# Power_Supply.net
KiCad netlist of a schematic drawn in Altium Designer
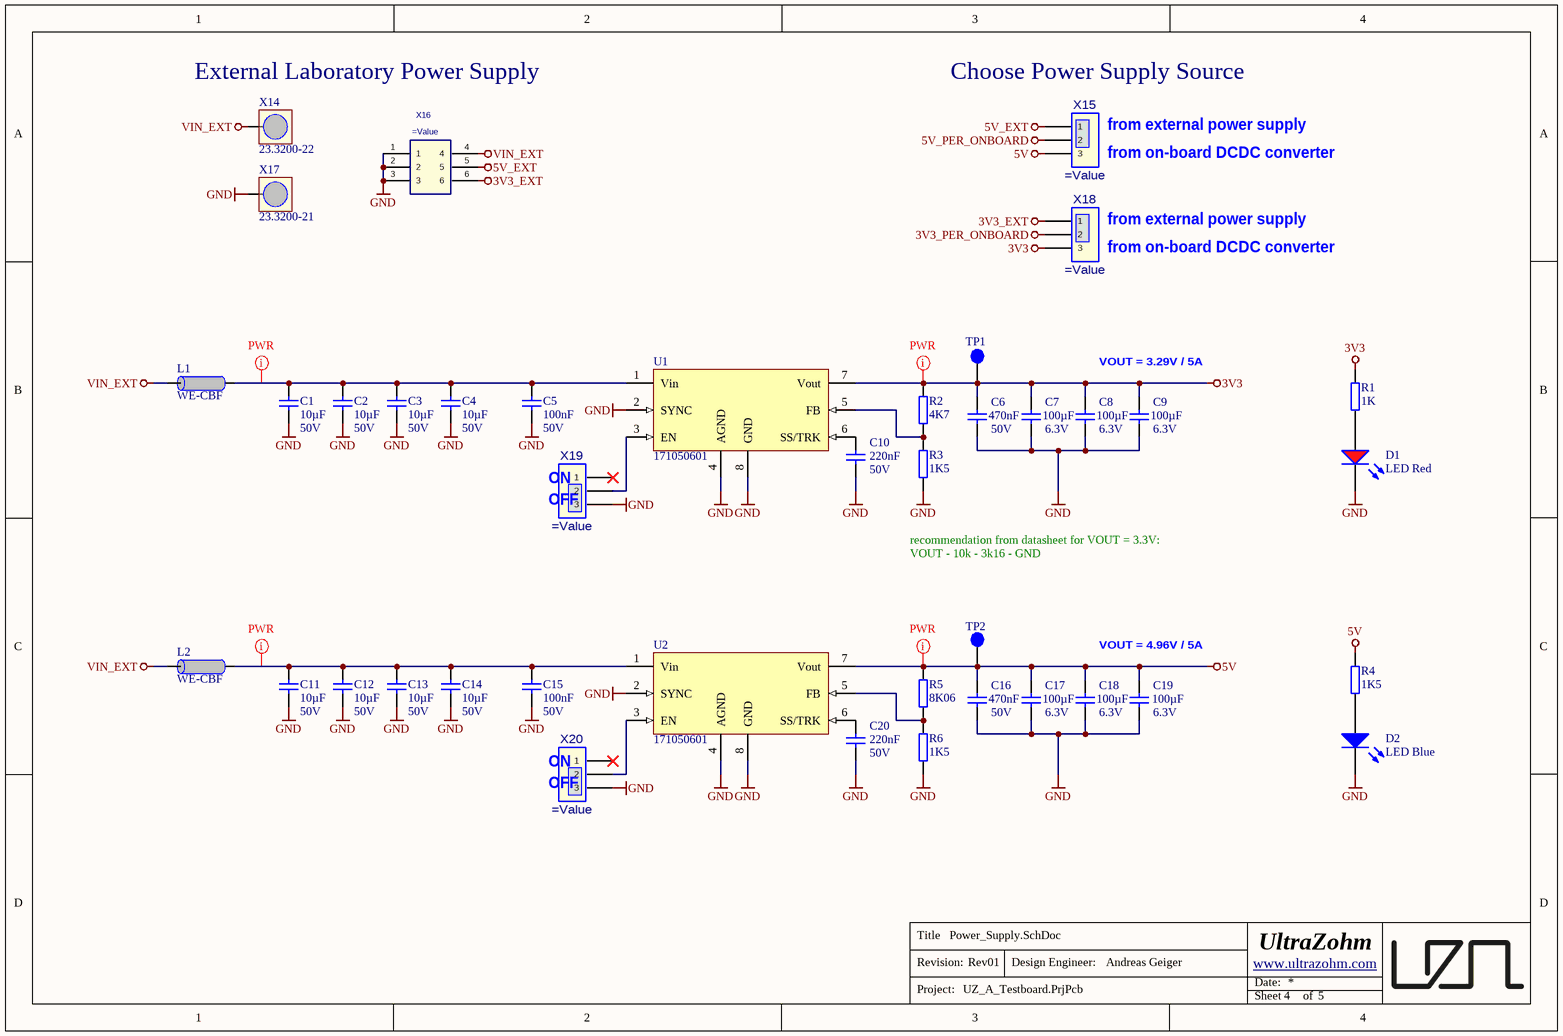
[diagram p0: Power_Supply.SchDoc]

(export (version "E")
  (design (tool "Eeschema 10.0.6"))
  (components
    (comp (ref "C1")
      (value "10µF")
      (footprint "CAPC3216X180N_V")
      (description "KON 10µF 50V X5R 10%  SMD BF 3216 (1206)")
      (fields (field (name "VOLTAGE") "50V") (field (name "TOLERANCE") "10%"))
      (libsource (lib "TE") (part "CAP-NP"))
    )
    (comp (ref "C2")
      (value "10µF")
      (footprint "CAPC3216X180N_V")
      (description "KON 10µF 50V X5R 10%  SMD BF 3216 (1206)")
      (fields (field (name "VOLTAGE") "50V") (field (name "TOLERANCE") "10%"))
      (libsource (lib "TE") (part "CAP-NP"))
    )
    (comp (ref "C3")
      (value "10µF")
      (footprint "CAPC3216X180N_V")
      (description "KON 10µF 50V X5R 10%  SMD BF 3216 (1206)")
      (fields (field (name "VOLTAGE") "50V") (field (name "TOLERANCE") "10%"))
      (libsource (lib "TE") (part "CAP-NP"))
    )
    (comp (ref "C4")
      (value "10µF")
      (footprint "CAPC3216X180N_V")
      (description "KON 10µF 50V X5R 10%  SMD BF 3216 (1206)")
      (fields (field (name "VOLTAGE") "50V") (field (name "TOLERANCE") "10%"))
      (libsource (lib "TE") (part "CAP-NP"))
    )
    (comp (ref "C5")
      (value "100nF")
      (footprint "CAPC1608X90N_V")
      (description "KON 100nF 50V X7R ±10% SMD BF 1608 (0603)")
      (fields (field (name "TOLERANCE") "±10%") (field (name "VOLTAGE") "50V"))
      (libsource (lib "TE") (part "CAP-NP"))
    )
    (comp (ref "C6")
      (value "470nF")
      (footprint "CAPC1608X90N_V")
      (description "KON 470nF 50V X7R SMD  BF 1608 (0603)")
      (fields (field (name "VOLTAGE") "50V"))
      (libsource (lib "TE") (part "CAP-NP"))
    )
    (comp (ref "C7")
      (value "100µF")
      (footprint "CAPC3216X180N_V")
      (description "KON 100µF 6,3V X5R 20% SMD BF 3216 (1206)")
      (fields (field (name "VOLTAGE") "6.3V") (field (name "TOLERANCE") "20%"))
      (libsource (lib "TE") (part "CAP-NP"))
    )
    (comp (ref "C8")
      (value "100µF")
      (footprint "CAPC3216X180N_V")
      (description "KON 100µF 6,3V X5R 20% SMD BF 3216 (1206)")
      (fields (field (name "VOLTAGE") "6.3V") (field (name "TOLERANCE") "20%"))
      (libsource (lib "TE") (part "CAP-NP"))
    )
    (comp (ref "C9")
      (value "100µF")
      (footprint "CAPC3216X180N_V")
      (description "KON 100µF 6,3V X5R 20% SMD BF 3216 (1206)")
      (fields (field (name "VOLTAGE") "6.3V") (field (name "TOLERANCE") "20%"))
      (libsource (lib "TE") (part "CAP-NP"))
    )
    (comp (ref "C10")
      (value "220nF")
      (footprint "CAPC1608X90N_V")
      (description "KON 220nF 50V X7R ±10% SMD BF 1608 (0603)")
      (fields (field (name "TOLERANCE") "±10%") (field (name "VOLTAGE") "50V"))
      (libsource (lib "TE") (part "CAP-NP"))
    )
    (comp (ref "C11")
      (value "10µF")
      (footprint "CAPC3216X180N_V")
      (description "KON 10µF 50V X5R 10%  SMD BF 3216 (1206)")
      (fields (field (name "VOLTAGE") "50V") (field (name "TOLERANCE") "10%"))
      (libsource (lib "TE") (part "CAP-NP"))
    )
    (comp (ref "C12")
      (value "10µF")
      (footprint "CAPC3216X180N_V")
      (description "KON 10µF 50V X5R 10%  SMD BF 3216 (1206)")
      (fields (field (name "VOLTAGE") "50V") (field (name "TOLERANCE") "10%"))
      (libsource (lib "TE") (part "CAP-NP"))
    )
    (comp (ref "C13")
      (value "10µF")
      (footprint "CAPC3216X180N_V")
      (description "KON 10µF 50V X5R 10%  SMD BF 3216 (1206)")
      (fields (field (name "VOLTAGE") "50V") (field (name "TOLERANCE") "10%"))
      (libsource (lib "TE") (part "CAP-NP"))
    )
    (comp (ref "C14")
      (value "10µF")
      (footprint "CAPC3216X180N_V")
      (description "KON 10µF 50V X5R 10%  SMD BF 3216 (1206)")
      (fields (field (name "VOLTAGE") "50V") (field (name "TOLERANCE") "10%"))
      (libsource (lib "TE") (part "CAP-NP"))
    )
    (comp (ref "C15")
      (value "100nF")
      (footprint "CAPC1608X90N_V")
      (description "KON 100nF 50V X7R ±10% SMD BF 1608 (0603)")
      (fields (field (name "TOLERANCE") "±10%") (field (name "VOLTAGE") "50V"))
      (libsource (lib "TE") (part "CAP-NP"))
    )
    (comp (ref "C16")
      (value "470nF")
      (footprint "CAPC1608X90N_V")
      (description "KON 470nF 50V X7R SMD  BF 1608 (0603)")
      (fields (field (name "VOLTAGE") "50V"))
      (libsource (lib "TE") (part "CAP-NP"))
    )
    (comp (ref "C17")
      (value "100µF")
      (footprint "CAPC3216X180N_V")
      (description "KON 100µF 6,3V X5R 20% SMD BF 3216 (1206)")
      (fields (field (name "VOLTAGE") "6.3V") (field (name "TOLERANCE") "20%"))
      (libsource (lib "TE") (part "CAP-NP"))
    )
    (comp (ref "C18")
      (value "100µF")
      (footprint "CAPC3216X180N_V")
      (description "KON 100µF 6,3V X5R 20% SMD BF 3216 (1206)")
      (fields (field (name "VOLTAGE") "6.3V") (field (name "TOLERANCE") "20%"))
      (libsource (lib "TE") (part "CAP-NP"))
    )
    (comp (ref "C19")
      (value "100µF")
      (footprint "CAPC3216X180N_V")
      (description "KON 100µF 6,3V X5R 20% SMD BF 3216 (1206)")
      (fields (field (name "VOLTAGE") "6.3V") (field (name "TOLERANCE") "20%"))
      (libsource (lib "TE") (part "CAP-NP"))
    )
    (comp (ref "C20")
      (value "220nF")
      (footprint "CAPC1608X90N_V")
      (description "KON 220nF 50V X7R ±10% SMD BF 1608 (0603)")
      (fields (field (name "TOLERANCE") "±10%") (field (name "VOLTAGE") "50V"))
      (libsource (lib "TE") (part "CAP-NP"))
    )
    (comp (ref "D1")
      (value "LED Red")
      (footprint "WL-SMCW_0603")
      (description "LED RED 520~625NM 90~100MCD@20MA TOP VIEW 0603 ROHS")
      (fields
        (field (name "MANUFACTURER PART NUMBER") "KT-0603R")
        (field (name "MANUFACTURER") "Hubei KENTO Elec")
        (field (name "CREATED FROM") "T. Wendt")
      )
      (libsource (lib "user") (part "LED_Red"))
    )
    (comp (ref "D2")
      (value "LED Blue")
      (footprint "WL-SMCW_0603")
      (description "LED BLUE 465~475NM 11.5~28.5MCD@5MA TOP VIEW 0603 ROHS")
      (fields
        (field (name "MANUFACTURER PART NUMBER") "19-217/BHC-ZL1M2RY/3T")
        (field (name "MANUFACTURER") "Everlight Elec")
        (field (name "CREATED FROM") "T. Wendt")
      )
      (libsource (lib "user") (part "LED_Blue"))
    )
    (comp (ref "L1")
      (value "WE-CBF")
      (footprint "INDC2012X92N_V")
      (description "Ferritdurchführung SMD 0805")
      (fields (field (name "VOLTAGE") "2000mA"))
      (libsource (lib "TE") (part "Ferritperle"))
    )
    (comp (ref "L2")
      (value "WE-CBF")
      (footprint "INDC2012X92N_V")
      (description "Ferritdurchführung SMD 0805")
      (fields (field (name "VOLTAGE") "2000mA"))
      (libsource (lib "TE") (part "Ferritperle"))
    )
    (comp (ref "R1")
      (value "1K")
      (footprint "RESC1608X55N_V")
      (description "WID SMD 1K 1% 0,1W")
      (fields (field (name "TOLERANCE") "1%"))
      (libsource (lib "TE") (part "RES"))
    )
    (comp (ref "R2")
      (value "4K7")
      (footprint "RESC1608X55N_V")
      (description "WID SMD 4K7 1% 0,1W BF 1608 (0603)")
      (fields (field (name "TOLERANCE") "1%"))
      (libsource (lib "TE") (part "RES"))
    )
    (comp (ref "R3")
      (value "1K5")
      (footprint "RESC1608X55N_V")
      (description "WID SMD 1K5 1% 0,1W")
      (fields (field (name "TOLERANCE") "1%"))
      (libsource (lib "TE") (part "RES"))
    )
    (comp (ref "R4")
      (value "1K5")
      (footprint "RESC1608X55N_V")
      (description "WID SMD 1K5 1% 0,1W")
      (fields (field (name "TOLERANCE") "1%"))
      (libsource (lib "TE") (part "RES"))
    )
    (comp (ref "R5")
      (value "8K06")
      (footprint "RESC1608X55N_V")
      (description "WID SMD 8K06 1% 0,1W BF 1608 (0603)")
      (fields (field (name "TOLERANCE") "1%"))
      (libsource (lib "TE") (part "RES"))
    )
    (comp (ref "R6")
      (value "1K5")
      (footprint "RESC1608X55N_V")
      (description "WID SMD 1K5 1% 0,1W")
      (fields (field (name "TOLERANCE") "1%"))
      (libsource (lib "TE") (part "RES"))
    )
    (comp (ref "TP1") (value "Testpoint 1mm") (footprint "TP_1mm") (libsource (lib "TE") (part "TP")))
    (comp (ref "TP2") (value "Testpoint 1mm") (footprint "TP_1mm") (libsource (lib "TE") (part "TP")))
    (comp (ref "U1")
      (value "171050601")
      (footprint "7TO-PMOD")
      (fields (field (name "VOLTAGE") "Adj."))
      (libsource (lib "TE") (part "WE-DCDC-171050601"))
    )
    (comp (ref "U2")
      (value "171050601")
      (footprint "7TO-PMOD")
      (fields (field (name "VOLTAGE") "Adj."))
      (libsource (lib "TE") (part "WE-DCDC-171050601"))
    )
    (comp (ref "X14")
      (value "23.3200-22")
      (footprint "Bannanenbuchse Rot Stäubli 23.3200-22")
      (description "MULTI-CONTACT   23.3200-22   BANANA SOCKET, 24A, 4MM, THT, R/A, RED")
      (fields (field (name "MANUFACTURER") "Stäubli"))
      (libsource (lib "UZ_A_Testboard") (part "Banannenstecker-Buchse Stäubli Rot"))
    )
    (comp (ref "X15")
      (value "~")
      (footprint "TSW-103-XX-XXX-S")
      (description ".025[0.64] SQ. POST TERMINAL STRIP ASSEMBLY.")
      (fields
        (field (name "MANUFACTURER") "SAMTEC")
        (field (name "MPN") "TSW-103-07-F-S")
        (field (name "CREATED") "2020_11_26_AGeiger")
      )
      (libsource (lib "UZ_A_Testboard") (part "TSW-103-XX-XXX-S"))
    )
    (comp (ref "X16")
      (value "~")
      (footprint "IPL1-103-01-L-D-RA-K")
      (description "2.54mm Double Row Terminal Assembly")
      (fields (field (name "MF") "SAMTEC") (field (name "CREATED") "2018_05_02_AGeiger"))
      (libsource (lib "UZ_A_Testboard") (part "IPL1-103-XX-X-D-X"))
    )
    (comp (ref "X17")
      (value "23.3200-21")
      (footprint "Bannanenbuchse Schwarz Stäubli 23.3200-21")
      (description "MULTI-CONTACT   23.3200-21   BANANA SOCKET, 24A, 4MM, THT, R/A, Black")
      (fields (field (name "MANUFACTURER") "Stäubli"))
      (libsource (lib "UZ_A_Testboard") (part "Banannenstecker-Buchse Stäubli Schwarz"))
    )
    (comp (ref "X18")
      (value "~")
      (footprint "TSW-103-XX-XXX-S")
      (description ".025[0.64] SQ. POST TERMINAL STRIP ASSEMBLY.")
      (fields
        (field (name "MANUFACTURER") "SAMTEC")
        (field (name "MPN") "TSW-103-07-F-S")
        (field (name "CREATED") "2020_11_26_AGeiger")
      )
      (libsource (lib "UZ_A_Testboard") (part "TSW-103-XX-XXX-S"))
    )
    (comp (ref "X19")
      (value "~")
      (footprint "TSW-103-XX-XXX-S")
      (description ".025[0.64] SQ. POST TERMINAL STRIP ASSEMBLY.")
      (fields
        (field (name "MANUFACTURER") "SAMTEC")
        (field (name "MPN") "TSW-103-07-F-S")
        (field (name "CREATED") "2020_11_26_AGeiger")
      )
      (libsource (lib "") (part "TSW-103-XX-XXX-S_1"))
    )
    (comp (ref "X20")
      (value "~")
      (footprint "TSW-103-XX-XXX-S")
      (description ".025[0.64] SQ. POST TERMINAL STRIP ASSEMBLY.")
      (fields
        (field (name "MANUFACTURER") "SAMTEC")
        (field (name "MPN") "TSW-103-07-F-S")
        (field (name "CREATED") "2020_11_26_AGeiger")
      )
      (libsource (lib "") (part "TSW-103-XX-XXX-S_1"))
    )
  )
  (nets
    (net (code "1") (name "3V3") (class "Default")
      (node (ref "C6") (pin "1") (pinfunction "1_1") (pintype "passive"))
      (node (ref "C7") (pin "1") (pinfunction "1_1") (pintype "passive"))
      (node (ref "C8") (pin "1") (pinfunction "1_1") (pintype "passive"))
      (node (ref "C9") (pin "1") (pinfunction "1_1") (pintype "passive"))
      (node (ref "R1") (pin "2") (pinfunction "2_2") (pintype "passive"))
      (node (ref "R2") (pin "2") (pinfunction "2_2") (pintype "passive"))
      (node (ref "TP1") (pin "1") (pintype "passive"))
      (node (ref "U1") (pin "7") (pinfunction "Vout_7") (pintype "power_in"))
      (node (ref "X18") (pin "3") (pinfunction "3_3") (pintype "passive"))
    )
    (net (code "2") (name "3V3_EXT") (class "Default")
      (node (ref "X16") (pin "6") (pinfunction "6_6") (pintype "passive"))
      (node (ref "X18") (pin "1") (pinfunction "1_1") (pintype "passive"))
    )
    (net (code "3") (name "3V3_PER_ONBOARD") (class "Default")
      (node (ref "X18") (pin "2") (pinfunction "2_2") (pintype "passive"))
    )
    (net (code "4") (name "5V") (class "Default")
      (node (ref "C16") (pin "1") (pinfunction "1_1") (pintype "passive"))
      (node (ref "C17") (pin "1") (pinfunction "1_1") (pintype "passive"))
      (node (ref "C18") (pin "1") (pinfunction "1_1") (pintype "passive"))
      (node (ref "C19") (pin "1") (pinfunction "1_1") (pintype "passive"))
      (node (ref "R4") (pin "2") (pinfunction "2_2") (pintype "passive"))
      (node (ref "R5") (pin "2") (pinfunction "2_2") (pintype "passive"))
      (node (ref "TP2") (pin "1") (pintype "passive"))
      (node (ref "U2") (pin "7") (pinfunction "Vout_7") (pintype "power_in"))
      (node (ref "X15") (pin "3") (pinfunction "3_3") (pintype "passive"))
    )
    (net (code "5") (name "5V_EXT") (class "Default")
      (node (ref "X15") (pin "1") (pinfunction "1_1") (pintype "passive"))
      (node (ref "X16") (pin "5") (pinfunction "5_5") (pintype "passive"))
    )
    (net (code "6") (name "5V_PER_ONBOARD") (class "Default")
      (node (ref "X15") (pin "2") (pinfunction "2_2") (pintype "passive"))
    )
    (net (code "7") (name "GND") (class "Default")
      (node (ref "C1") (pin "2") (pinfunction "2_2") (pintype "passive"))
      (node (ref "C10") (pin "2") (pinfunction "2_2") (pintype "passive"))
      (node (ref "C11") (pin "2") (pinfunction "2_2") (pintype "passive"))
      (node (ref "C12") (pin "2") (pinfunction "2_2") (pintype "passive"))
      (node (ref "C13") (pin "2") (pinfunction "2_2") (pintype "passive"))
      (node (ref "C14") (pin "2") (pinfunction "2_2") (pintype "passive"))
      (node (ref "C15") (pin "1") (pinfunction "1_1") (pintype "passive"))
      (node (ref "C16") (pin "2") (pinfunction "2_2") (pintype "passive"))
      (node (ref "C17") (pin "2") (pinfunction "2_2") (pintype "passive"))
      (node (ref "C18") (pin "2") (pinfunction "2_2") (pintype "passive"))
      (node (ref "C19") (pin "2") (pinfunction "2_2") (pintype "passive"))
      (node (ref "C2") (pin "2") (pinfunction "2_2") (pintype "passive"))
      (node (ref "C20") (pin "2") (pinfunction "2_2") (pintype "passive"))
      (node (ref "C3") (pin "2") (pinfunction "2_2") (pintype "passive"))
      (node (ref "C4") (pin "2") (pinfunction "2_2") (pintype "passive"))
      (node (ref "C5") (pin "1") (pinfunction "1_1") (pintype "passive"))
      (node (ref "C6") (pin "2") (pinfunction "2_2") (pintype "passive"))
      (node (ref "C7") (pin "2") (pinfunction "2_2") (pintype "passive"))
      (node (ref "C8") (pin "2") (pinfunction "2_2") (pintype "passive"))
      (node (ref "C9") (pin "2") (pinfunction "2_2") (pintype "passive"))
      (node (ref "D1") (pin "1") (pinfunction "K_1") (pintype "passive"))
      (node (ref "D2") (pin "1") (pinfunction "K_1") (pintype "passive"))
      (node (ref "R3") (pin "1") (pinfunction "1_1") (pintype "passive"))
      (node (ref "R6") (pin "2") (pinfunction "2_2") (pintype "passive"))
      (node (ref "U1") (pin "2") (pinfunction "SYNC_2") (pintype "input"))
      (node (ref "U1") (pin "4") (pinfunction "AGND_4") (pintype "power_in"))
      (node (ref "U1") (pin "8") (pinfunction "GND_8") (pintype "power_in"))
      (node (ref "U2") (pin "2") (pinfunction "SYNC_2") (pintype "input"))
      (node (ref "U2") (pin "4") (pinfunction "AGND_4") (pintype "power_in"))
      (node (ref "U2") (pin "8") (pinfunction "GND_8") (pintype "power_in"))
      (node (ref "X16") (pin "1") (pinfunction "1_1") (pintype "passive"))
      (node (ref "X16") (pin "2") (pinfunction "2_2") (pintype "passive"))
      (node (ref "X16") (pin "3") (pinfunction "3_3") (pintype "passive"))
      (node (ref "X17") (pin "1") (pinfunction "1_1") (pintype "passive"))
      (node (ref "X19") (pin "3") (pinfunction "3_3") (pintype "passive"))
      (node (ref "X20") (pin "3") (pinfunction "3_3") (pintype "passive"))
    )
    (net (code "8") (name "Net-(D1-A)") (class "Default")
      (node (ref "D1") (pin "2") (pinfunction "A_2") (pintype "passive"))
      (node (ref "R1") (pin "1") (pinfunction "1_1") (pintype "passive"))
    )
    (net (code "9") (name "Net-(D2-A)") (class "Default")
      (node (ref "D2") (pin "2") (pinfunction "A_2") (pintype "passive"))
      (node (ref "R4") (pin "1") (pinfunction "1_1") (pintype "passive"))
    )
    (net (code "10") (name "Net-(U1-EN)") (class "Default")
      (node (ref "U1") (pin "3") (pinfunction "EN_3") (pintype "input"))
      (node (ref "X19") (pin "2") (pinfunction "2_2") (pintype "passive"))
    )
    (net (code "11") (name "Net-(U1-FB)") (class "Default")
      (node (ref "R2") (pin "1") (pinfunction "1_1") (pintype "passive"))
      (node (ref "R3") (pin "2") (pinfunction "2_2") (pintype "passive"))
      (node (ref "U1") (pin "5") (pinfunction "FB_5") (pintype "input"))
    )
    (net (code "12") (name "Net-(U1-SS{slash}TRK)") (class "Default")
      (node (ref "C10") (pin "1") (pinfunction "1_1") (pintype "passive"))
      (node (ref "U1") (pin "6") (pinfunction "SS/TRK_6") (pintype "input"))
    )
    (net (code "13") (name "Net-(U1-Vin)") (class "Default")
      (node (ref "C1") (pin "1") (pinfunction "1_1") (pintype "passive"))
      (node (ref "C2") (pin "1") (pinfunction "1_1") (pintype "passive"))
      (node (ref "C3") (pin "1") (pinfunction "1_1") (pintype "passive"))
      (node (ref "C4") (pin "1") (pinfunction "1_1") (pintype "passive"))
      (node (ref "C5") (pin "2") (pinfunction "2_2") (pintype "passive"))
      (node (ref "L1") (pin "1") (pinfunction "1_1") (pintype "passive"))
      (node (ref "U1") (pin "1") (pinfunction "Vin_1") (pintype "power_in"))
    )
    (net (code "14") (name "Net-(U2-EN)") (class "Default")
      (node (ref "U2") (pin "3") (pinfunction "EN_3") (pintype "input"))
      (node (ref "X20") (pin "2") (pinfunction "2_2") (pintype "passive"))
    )
    (net (code "15") (name "Net-(U2-FB)") (class "Default")
      (node (ref "R5") (pin "1") (pinfunction "1_1") (pintype "passive"))
      (node (ref "R6") (pin "1") (pinfunction "1_1") (pintype "passive"))
      (node (ref "U2") (pin "5") (pinfunction "FB_5") (pintype "input"))
    )
    (net (code "16") (name "Net-(U2-SS{slash}TRK)") (class "Default")
      (node (ref "C20") (pin "1") (pinfunction "1_1") (pintype "passive"))
      (node (ref "U2") (pin "6") (pinfunction "SS/TRK_6") (pintype "input"))
    )
    (net (code "17") (name "Net-(U2-Vin)") (class "Default")
      (node (ref "C11") (pin "1") (pinfunction "1_1") (pintype "passive"))
      (node (ref "C12") (pin "1") (pinfunction "1_1") (pintype "passive"))
      (node (ref "C13") (pin "1") (pinfunction "1_1") (pintype "passive"))
      (node (ref "C14") (pin "1") (pinfunction "1_1") (pintype "passive"))
      (node (ref "C15") (pin "2") (pinfunction "2_2") (pintype "passive"))
      (node (ref "L2") (pin "1") (pinfunction "1_1") (pintype "passive"))
      (node (ref "U2") (pin "1") (pinfunction "Vin_1") (pintype "power_in"))
    )
    (net (code "18") (name "VIN_EXT") (class "Default")
      (node (ref "L1") (pin "2") (pinfunction "2_2") (pintype "passive"))
      (node (ref "L2") (pin "2") (pinfunction "2_2") (pintype "passive"))
      (node (ref "X14") (pin "1") (pinfunction "1_1") (pintype "passive"))
      (node (ref "X16") (pin "4") (pinfunction "4_4") (pintype "passive"))
    )
    (net (code "19") (name "unconnected-(X19-Pad1)") (class "Default")
      (node (ref "X19") (pin "1") (pinfunction "1_1") (pintype "passive+no_connect"))
    )
    (net (code "20") (name "unconnected-(X20-Pad1)") (class "Default")
      (node (ref "X20") (pin "1") (pinfunction "1_1") (pintype "passive+no_connect"))
    )
  )
)
